# 06_-_CPU_-_ETHERNET_SATA.net
KiCad netlist of a schematic drawn in Altium Designer
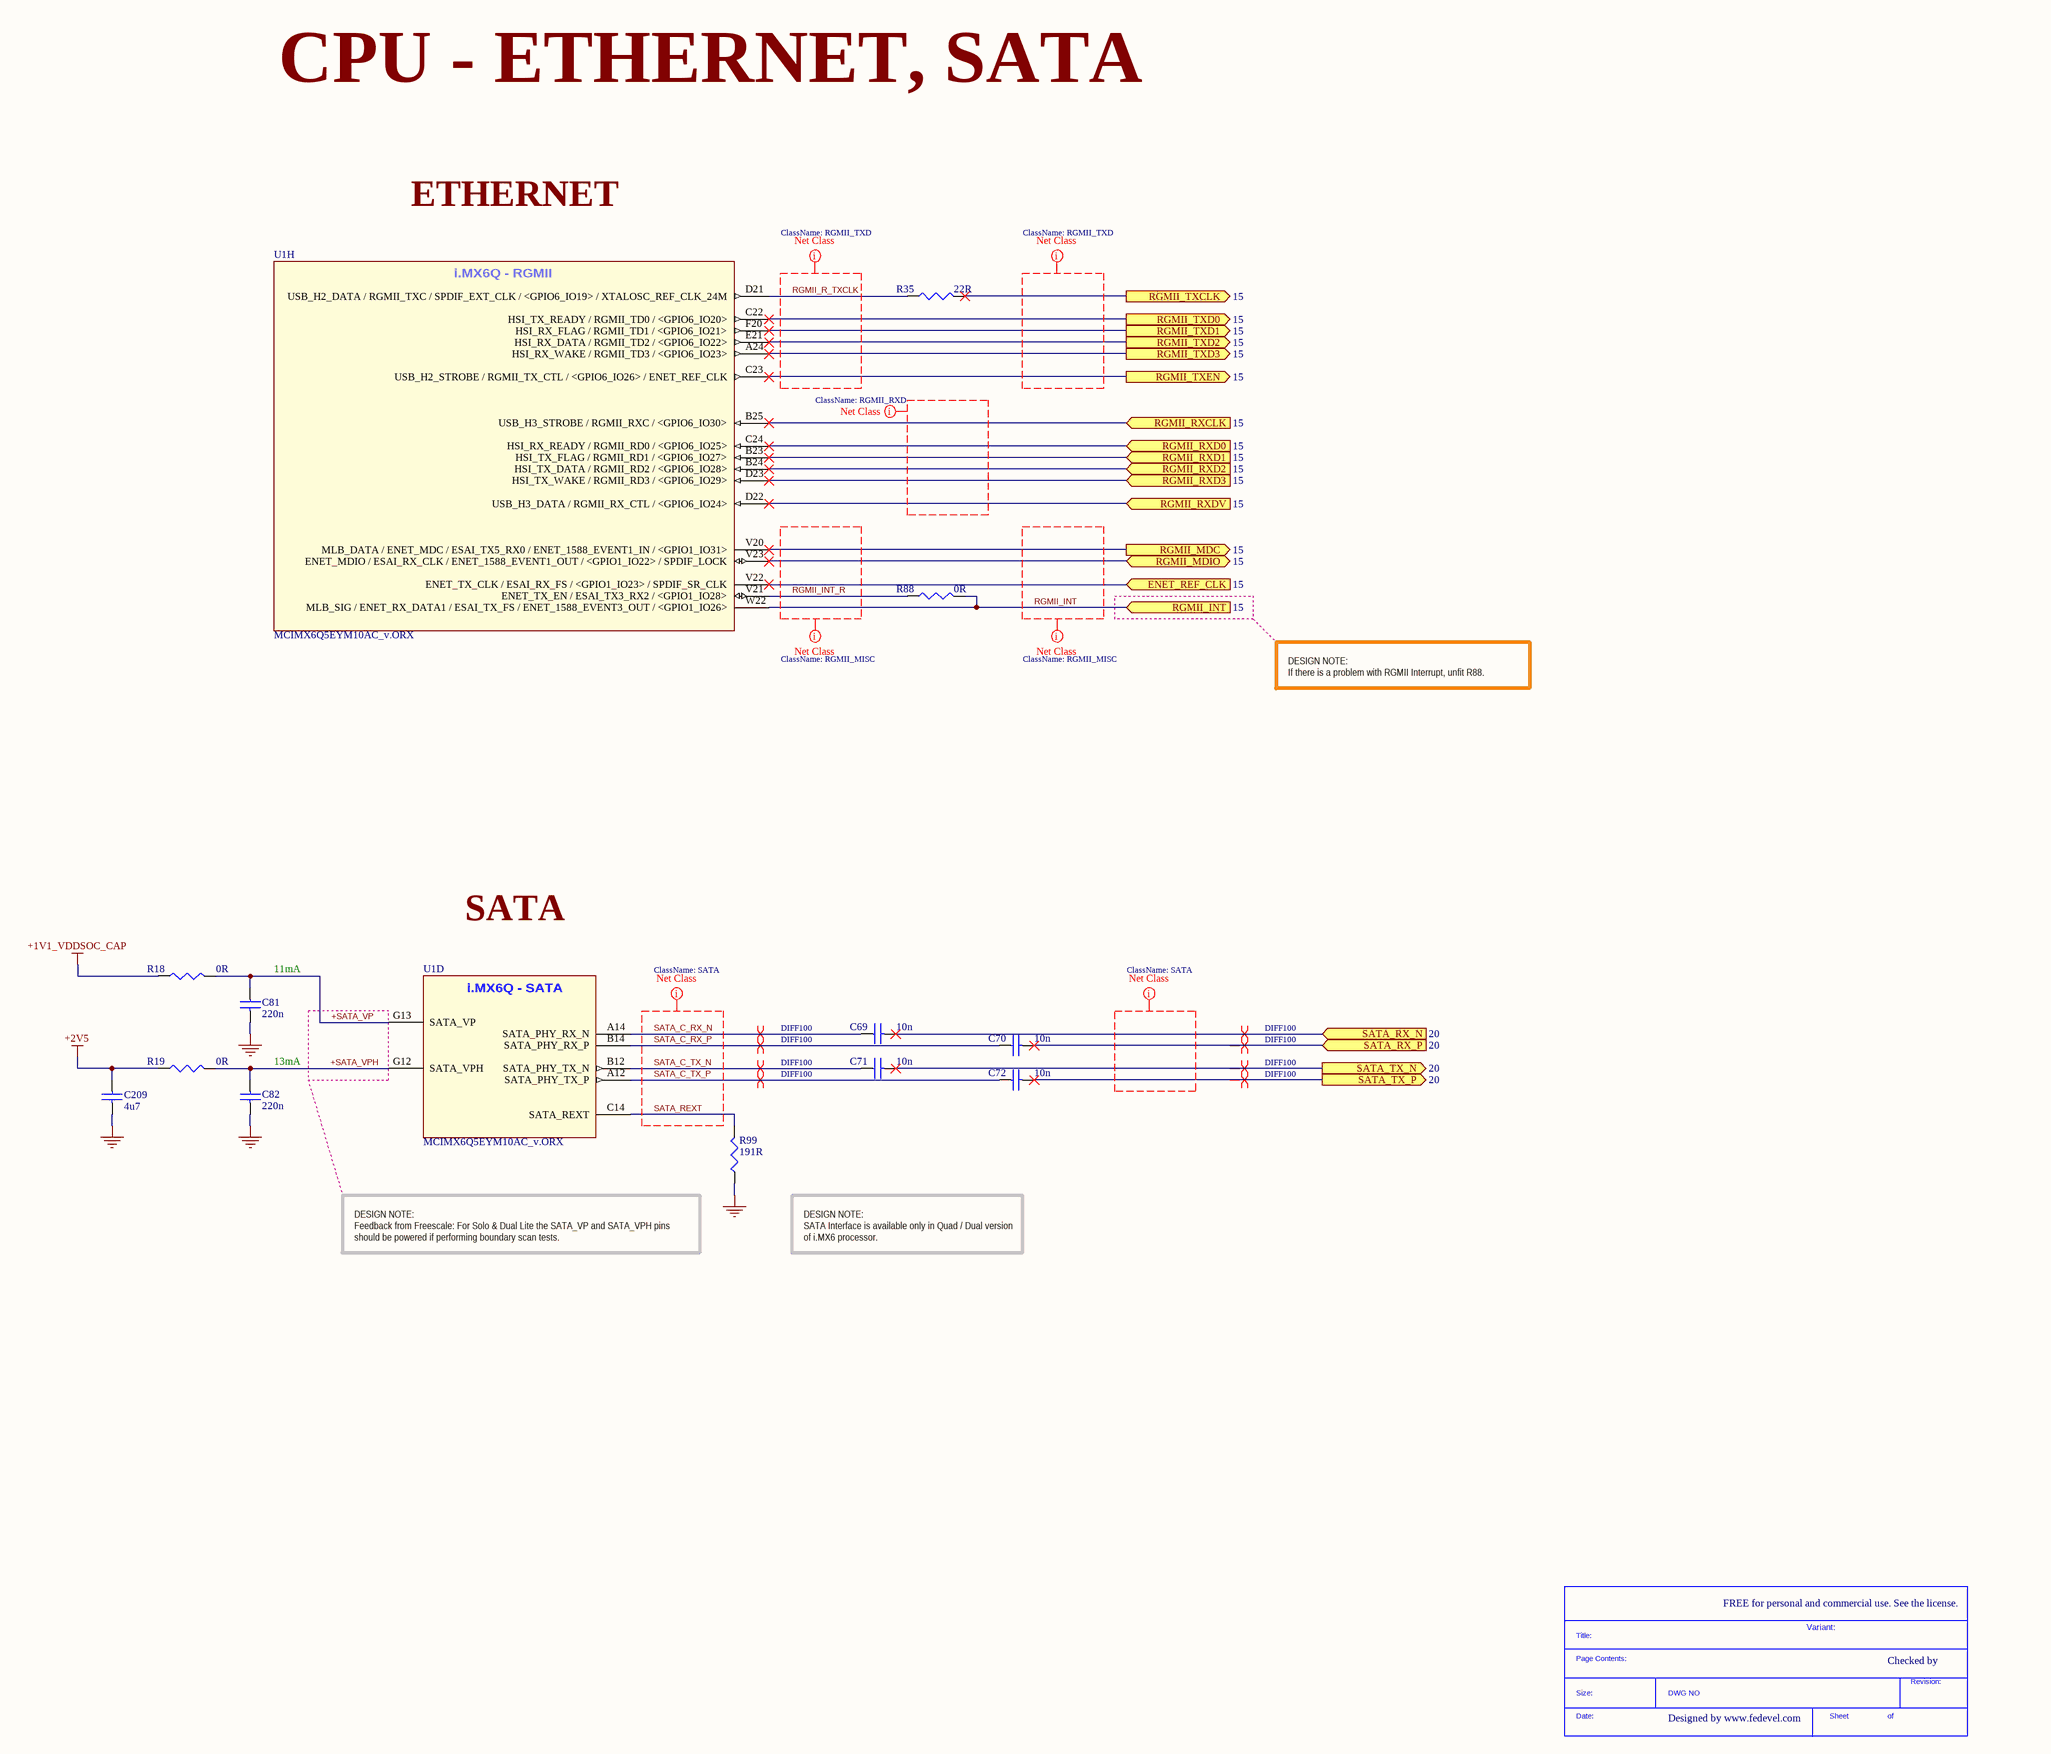
[diagram p0: [06] - CPU - ETHERNET, SATA.SchDoc]

(export (version "E")
  (design (tool "Eeschema 10.0.6"))
  (components
    (comp (ref "C69")
      (value "10n")
      (footprint "C0402")
      (description "CAP CER 10000PF 50V 10% X7R 0402")
      (fields
        (field (name "MANUFACTURER") "TDK Corporation")
        (field (name "MANUFACTURER PART NUMBER") "C1005X7R1H103K")
      )
      (libsource (lib "Integrated_Library_FEDEVEL_APR_2015") (part "C1005X7R1H103K"))
    )
    (comp (ref "C70")
      (value "10n")
      (footprint "C0402")
      (description "CAP CER 10000PF 50V 10% X7R 0402")
      (fields
        (field (name "MANUFACTURER") "TDK Corporation")
        (field (name "MANUFACTURER PART NUMBER") "C1005X7R1H103K")
      )
      (libsource (lib "Integrated_Library_FEDEVEL_APR_2015") (part "C1005X7R1H103K"))
    )
    (comp (ref "C71")
      (value "10n")
      (footprint "C0402")
      (description "CAP CER 10000PF 50V 10% X7R 0402")
      (fields
        (field (name "MANUFACTURER") "TDK Corporation")
        (field (name "MANUFACTURER PART NUMBER") "C1005X7R1H103K")
      )
      (libsource (lib "Integrated_Library_FEDEVEL_APR_2015") (part "C1005X7R1H103K"))
    )
    (comp (ref "C72")
      (value "10n")
      (footprint "C0402")
      (description "CAP CER 10000PF 50V 10% X7R 0402")
      (fields
        (field (name "MANUFACTURER") "TDK Corporation")
        (field (name "MANUFACTURER PART NUMBER") "C1005X7R1H103K")
      )
      (libsource (lib "Integrated_Library_FEDEVEL_APR_2015") (part "C1005X7R1H103K"))
    )
    (comp (ref "C81")
      (value "220n")
      (footprint "C0201")
      (description "CAP CER 0.22UF 6.3V 20% X5R 0201")
      (fields
        (field (name "MANUFACTURER") "TDK Corporation")
        (field (name "MANUFACTURER PART NUMBER") "C0603X5R0J224M030BB")
        (field (name ".CHECKED PCB") "MM")
        (field (name ".CHECKED SCH") "MM")
        (field (name ".CREATOR") "MM")
      )
      (libsource (lib "Integrated_Library_FEDEVEL_0201") (part "C0603X5R0J224M030BB"))
    )
    (comp (ref "C82")
      (value "220n")
      (footprint "C0201")
      (description "CAP CER 0.22UF 6.3V 20% X5R 0201")
      (fields
        (field (name "MANUFACTURER") "TDK Corporation")
        (field (name "MANUFACTURER PART NUMBER") "C0603X5R0J224M030BB")
        (field (name ".CHECKED PCB") "MM")
        (field (name ".CHECKED SCH") "MM")
        (field (name ".CREATOR") "MM")
      )
      (libsource (lib "Integrated_Library_FEDEVEL_0201") (part "C0603X5R0J224M030BB"))
    )
    (comp (ref "C209")
      (value "4u7")
      (footprint "C0402")
      (description "CAP CER 4.7UF 10V 20% X5R 0402")
      (fields
        (field (name "MANUFACTURER") "TDK Corporation")
        (field (name "MANUFACTURER PART NUMBER") "C1005X5R1A475M")
      )
      (libsource (lib "Integrated_Library_FEDEVEL_APR_2015") (part "C1005X5R1A475M"))
    )
    (comp (ref "R18")
      (value "0R")
      (footprint "R0402")
      (description "RES 0.0 OHM 1/16W 0402 SMD")
      (fields
        (field (name "MANUFACTURER") "Yageo")
        (field (name "MANUFACTURER PART NUMBER") "RC0402JR-070RL")
      )
      (libsource (lib "Integrated_Library_FEDEVEL_APR_2015") (part "RC0402JR-070RL"))
    )
    (comp (ref "R19")
      (value "0R")
      (footprint "R0402")
      (description "RES 0.0 OHM 1/16W 0402 SMD")
      (fields
        (field (name "MANUFACTURER") "Yageo")
        (field (name "MANUFACTURER PART NUMBER") "RC0402JR-070RL")
      )
      (libsource (lib "Integrated_Library_FEDEVEL_APR_2015") (part "RC0402JR-070RL"))
    )
    (comp (ref "R35")
      (value "22R")
      (footprint "R0402")
      (description "RES 22.0 OHM 1/16W 1% 0402 SMD")
      (fields
        (field (name "MANUFACTURER") "Yageo")
        (field (name "MANUFACTURER PART NUMBER") "RC0402FR-0722RL")
      )
      (libsource (lib "Integrated_Library_FEDEVEL_APR_2015") (part "RC0402FR-0722RL"))
    )
    (comp (ref "R88")
      (value "0R")
      (footprint "R0402")
      (description "RES 0.0 OHM 1/16W 0402 SMD")
      (fields
        (field (name "MANUFACTURER") "Yageo")
        (field (name "MANUFACTURER PART NUMBER") "RC0402JR-070RL")
      )
      (libsource (lib "Integrated_Library_FEDEVEL_APR_2015") (part "RC0402JR-070RL"))
    )
    (comp (ref "R99")
      (value "191R")
      (footprint "R0201")
      (description "RES 191 OHM 1/20W 1% 0201 SMD")
      (fields
        (field (name "MANUFACTURER") "Panasonic Electronic Components")
        (field (name "MANUFACTURER PART NUMBER") "ERJ-1GEF1910C")
        (field (name ".CREATOR") "MM")
        (field (name ".CHECKED PCB") "MM")
        (field (name ".CHECKED SCH") "MM")
      )
      (libsource (lib "Integrated_Library_FEDEVEL_0201") (part "ERJ-1GEF1910C"))
    )
    (comp (ref "U1")
      (value "MCIMX6Q5EYM10AC_v.ORX")
      (footprint "PBGA624")
      (description "IC MCU 32BIT ARM QUAD 624FCBGA")
      (fields
        (field (name "MANUFACTURER") "Freescale Semiconductor")
        (field (name "MANUFACTURER PART NUMBER") "MCIMX6Q5EYM10AC")
        (field (name ".CREATOR") "MM")
        (field (name ".CHECKED PCB") "MM, checked by RF")
      )
      (libsource (lib "Integrated_Library_FEDEVEL_APR_2015") (part "MCIMX6Q5EYM10AC_v.ORX"))
    )
  )
  (nets
    (net (code "1") (name "+1V1_VDDSOC_CAP") (class "Default")
      (node (ref "R18") (pin "1") (pinfunction "1_1") (pintype "passive"))
    )
    (net (code "2") (name "+2V5") (class "Default")
      (node (ref "C209") (pin "1") (pinfunction "1_1") (pintype "passive"))
      (node (ref "R19") (pin "1") (pinfunction "1_1") (pintype "passive"))
    )
    (net (code "3") (name "/+SATA_VP") (class "Default")
      (node (ref "C81") (pin "1") (pinfunction "1_1") (pintype "passive"))
      (node (ref "R18") (pin "2") (pinfunction "2_2") (pintype "passive"))
      (node (ref "U1") (pin "G13") (pinfunction "SATA_VP_G13") (pintype "power_in"))
    )
    (net (code "4") (name "/+SATA_VPH") (class "Default")
      (node (ref "C82") (pin "1") (pinfunction "1_1") (pintype "passive"))
      (node (ref "R19") (pin "2") (pinfunction "2_2") (pintype "passive"))
      (node (ref "U1") (pin "G12") (pinfunction "SATA_VPH_G12") (pintype "power_in"))
    )
    (net (code "5") (name "/ENET_REF_CLK") (class "Default")
      (node (ref "U1") (pin "V22") (pinfunction "ENET_TX_CLK_/_ESAI_RX_FS_/_<GPIO1_IO23>_/_SPDIF_SR_CLK_V22") (pintype "passive+no_connect"))
    )
    (net (code "6") (name "/RGMII_INT") (class "Default")
      (node (ref "R88") (pin "2") (pinfunction "2_2") (pintype "passive"))
      (node (ref "U1") (pin "W22") (pinfunction "MLB_SIG_/_ENET_RX_DATA1_/_ESAI_TX_FS_/_ENET_1588_EVENT3_OUT_/_<GPIO1_IO26>_W22") (pintype "passive"))
    )
    (net (code "7") (name "/RGMII_INT_R") (class "Default")
      (node (ref "R88") (pin "1") (pinfunction "1_1") (pintype "passive"))
      (node (ref "U1") (pin "V21") (pinfunction "ENET_TX_EN_/_ESAI_TX3_RX2_/_<GPIO1_IO28>_V21") (pintype "bidirectional"))
    )
    (net (code "8") (name "/RGMII_MDC") (class "Default")
      (node (ref "U1") (pin "V20") (pinfunction "MLB_DATA_/_ENET_MDC_/_ESAI_TX5_RX0_/_ENET_1588_EVENT1_IN_/_<GPIO1_IO31>_V20") (pintype "passive+no_connect"))
    )
    (net (code "9") (name "/RGMII_MDIO") (class "Default")
      (node (ref "U1") (pin "V23") (pinfunction "ENET_MDIO_/_ESAI_RX_CLK_/_ENET_1588_EVENT1_OUT_/_<GPIO1_IO22>_/_SPDIF_LOCK_V23") (pintype "bidirectional+no_connect"))
    )
    (net (code "10") (name "/RGMII_RXCLK") (class "Default")
      (node (ref "U1") (pin "B25") (pinfunction "USB_H3_STROBE_/_RGMII_RXC_/_<GPIO6_IO30>_B25") (pintype "input+no_connect"))
    )
    (net (code "11") (name "/RGMII_RXD0") (class "Default")
      (node (ref "U1") (pin "C24") (pinfunction "HSI_RX_READY_/_RGMII_RD0_/_<GPIO6_IO25>_C24") (pintype "input+no_connect"))
    )
    (net (code "12") (name "/RGMII_RXD1") (class "Default")
      (node (ref "U1") (pin "B23") (pinfunction "HSI_TX_FLAG_/_RGMII_RD1_/_<GPIO6_IO27>_B23") (pintype "input+no_connect"))
    )
    (net (code "13") (name "/RGMII_RXD2") (class "Default")
      (node (ref "U1") (pin "B24") (pinfunction "HSI_TX_DATA_/_RGMII_RD2_/_<GPIO6_IO28>_B24") (pintype "input+no_connect"))
    )
    (net (code "14") (name "/RGMII_RXD3") (class "Default")
      (node (ref "U1") (pin "D23") (pinfunction "HSI_TX_WAKE_/_RGMII_RD3_/_<GPIO6_IO29>_D23") (pintype "input+no_connect"))
    )
    (net (code "15") (name "/RGMII_RXDV") (class "Default")
      (node (ref "U1") (pin "D22") (pinfunction "USB_H3_DATA_/_RGMII_RX_CTL_/_<GPIO6_IO24>_D22") (pintype "input+no_connect"))
    )
    (net (code "16") (name "/RGMII_R_TXCLK") (class "Default")
      (node (ref "R35") (pin "1") (pinfunction "1_1") (pintype "passive"))
      (node (ref "U1") (pin "D21") (pinfunction "USB_H2_DATA_/_RGMII_TXC_/_SPDIF_EXT_CLK_/_<GPIO6_IO19>_/_XTALOSC_REF_CLK_24M_D21") (pintype "output"))
    )
    (net (code "17") (name "/RGMII_TXCLK") (class "Default")
      (node (ref "R35") (pin "2") (pinfunction "2_2") (pintype "passive+no_connect"))
    )
    (net (code "18") (name "/RGMII_TXD0") (class "Default")
      (node (ref "U1") (pin "C22") (pinfunction "HSI_TX_READY_/_RGMII_TD0_/_<GPIO6_IO20>_C22") (pintype "output+no_connect"))
    )
    (net (code "19") (name "/RGMII_TXD1") (class "Default")
      (node (ref "U1") (pin "F20") (pinfunction "HSI_RX_FLAG_/_RGMII_TD1_/_<GPIO6_IO21>_F20") (pintype "output+no_connect"))
    )
    (net (code "20") (name "/RGMII_TXD2") (class "Default")
      (node (ref "U1") (pin "E21") (pinfunction "HSI_RX_DATA_/_RGMII_TD2_/_<GPIO6_IO22>_E21") (pintype "output+no_connect"))
    )
    (net (code "21") (name "/RGMII_TXD3") (class "Default")
      (node (ref "U1") (pin "A24") (pinfunction "HSI_RX_WAKE_/_RGMII_TD3_/_<GPIO6_IO23>_A24") (pintype "output+no_connect"))
    )
    (net (code "22") (name "/RGMII_TXEN") (class "Default")
      (node (ref "U1") (pin "C23") (pinfunction "USB_H2_STROBE_/_RGMII_TX_CTL_/_<GPIO6_IO26>_/_ENET_REF_CLK_C23") (pintype "output+no_connect"))
    )
    (net (code "23") (name "/SATA_C_RX_N") (class "Default")
      (node (ref "C69") (pin "1") (pinfunction "1_1") (pintype "passive"))
      (node (ref "U1") (pin "A14") (pinfunction "SATA_PHY_RX_N_A14") (pintype "passive"))
    )
    (net (code "24") (name "/SATA_C_RX_P") (class "Default")
      (node (ref "C70") (pin "1") (pinfunction "1_1") (pintype "passive"))
      (node (ref "U1") (pin "B14") (pinfunction "SATA_PHY_RX_P_B14") (pintype "passive"))
    )
    (net (code "25") (name "/SATA_C_TX_N") (class "Default")
      (node (ref "C71") (pin "1") (pinfunction "1_1") (pintype "passive"))
      (node (ref "U1") (pin "B12") (pinfunction "SATA_PHY_TX_N_B12") (pintype "output"))
    )
    (net (code "26") (name "/SATA_C_TX_P") (class "Default")
      (node (ref "C72") (pin "1") (pinfunction "1_1") (pintype "passive"))
      (node (ref "U1") (pin "A12") (pinfunction "SATA_PHY_TX_P_A12") (pintype "output"))
    )
    (net (code "27") (name "/SATA_REXT") (class "Default")
      (node (ref "R99") (pin "2") (pinfunction "2_2") (pintype "passive"))
      (node (ref "U1") (pin "C14") (pinfunction "SATA_REXT_C14") (pintype "passive"))
    )
    (net (code "28") (name "/SATA_RX_N") (class "Default")
      (node (ref "C69") (pin "2") (pinfunction "2_2") (pintype "passive+no_connect"))
    )
    (net (code "29") (name "/SATA_RX_P") (class "Default")
      (node (ref "C70") (pin "2") (pinfunction "2_2") (pintype "passive+no_connect"))
    )
    (net (code "30") (name "/SATA_TX_N") (class "Default")
      (node (ref "C71") (pin "2") (pinfunction "2_2") (pintype "passive+no_connect"))
    )
    (net (code "31") (name "/SATA_TX_P") (class "Default")
      (node (ref "C72") (pin "2") (pinfunction "2_2") (pintype "passive+no_connect"))
    )
    (net (code "32") (name "GND") (class "Default")
      (node (ref "C209") (pin "2") (pinfunction "2_2") (pintype "passive"))
      (node (ref "C81") (pin "2") (pinfunction "2_2") (pintype "passive"))
      (node (ref "C82") (pin "2") (pinfunction "2_2") (pintype "passive"))
      (node (ref "R99") (pin "1") (pinfunction "1_1") (pintype "passive"))
    )
  )
)
